# 02-CPU.net
KiCad netlist of a schematic drawn in Altium Designer
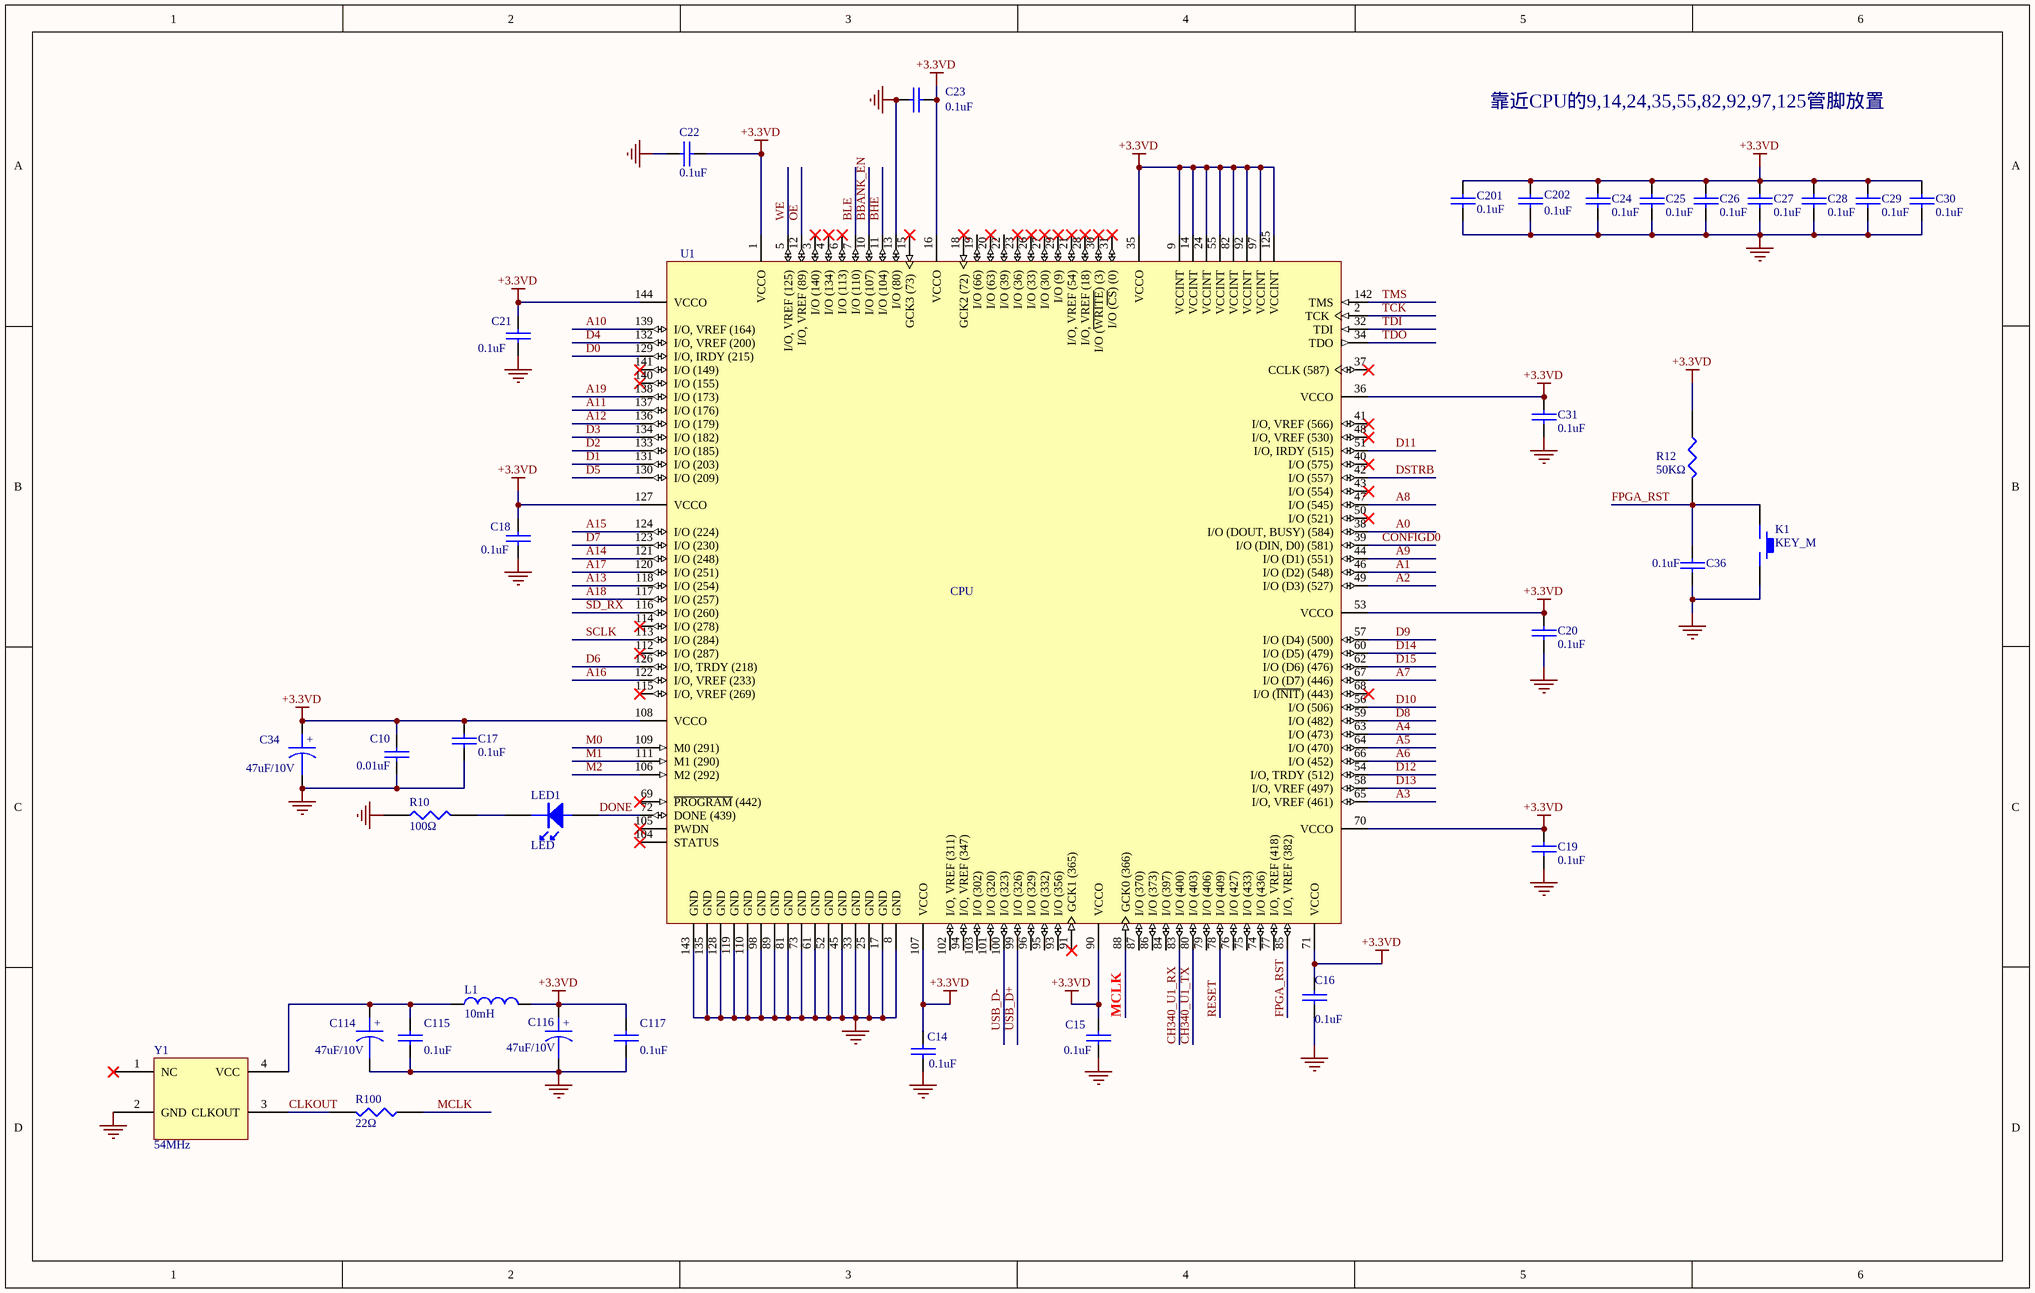
[diagram p0: 02-CPU.schdoc]

(export (version "E")
  (design (tool "Eeschema 10.0.6"))
  (components
    (comp (ref "C10")
      (value "0.01uF")
      (footprint "0603")
      (description "Capacitor")
      (libsource (lib "*") (part "CAP"))
    )
    (comp (ref "C14")
      (value "0.1uF")
      (footprint "0603")
      (description "Capacitor")
      (libsource (lib "*") (part "CAP"))
    )
    (comp (ref "C15")
      (value "0.1uF")
      (footprint "0603")
      (description "Capacitor")
      (libsource (lib "*") (part "CAP"))
    )
    (comp (ref "C16")
      (value "0.1uF")
      (footprint "0603")
      (description "Capacitor")
      (libsource (lib "*") (part "CAP"))
    )
    (comp (ref "C17")
      (value "0.1uF")
      (footprint "0603")
      (description "Capacitor")
      (libsource (lib "*") (part "CAP"))
    )
    (comp (ref "C18")
      (value "0.1uF")
      (footprint "0603")
      (description "Capacitor")
      (libsource (lib "*") (part "CAP"))
    )
    (comp (ref "C19")
      (value "0.1uF")
      (footprint "0603")
      (description "Capacitor")
      (libsource (lib "*") (part "CAP"))
    )
    (comp (ref "C20")
      (value "0.1uF")
      (footprint "0603")
      (description "Capacitor")
      (libsource (lib "*") (part "CAP"))
    )
    (comp (ref "C21")
      (value "0.1uF")
      (footprint "0603")
      (description "Capacitor")
      (libsource (lib "*") (part "CAP"))
    )
    (comp (ref "C22")
      (value "0.1uF")
      (footprint "0603")
      (description "Capacitor")
      (libsource (lib "*") (part "CAP"))
    )
    (comp (ref "C23")
      (value "0.1uF")
      (footprint "0603")
      (description "Capacitor")
      (libsource (lib "*") (part "CAP"))
    )
    (comp (ref "C24")
      (value "0.1uF")
      (footprint "0603")
      (description "Capacitor")
      (libsource (lib "*") (part "CAP"))
    )
    (comp (ref "C25")
      (value "0.1uF")
      (footprint "0603")
      (description "Capacitor")
      (libsource (lib "*") (part "CAP"))
    )
    (comp (ref "C26")
      (value "0.1uF")
      (footprint "0603")
      (description "Capacitor")
      (libsource (lib "*") (part "CAP"))
    )
    (comp (ref "C27")
      (value "0.1uF")
      (footprint "0603")
      (description "Capacitor")
      (libsource (lib "*") (part "CAP"))
    )
    (comp (ref "C28")
      (value "0.1uF")
      (footprint "0603")
      (description "Capacitor")
      (libsource (lib "*") (part "CAP"))
    )
    (comp (ref "C29")
      (value "0.1uF")
      (footprint "0603")
      (description "Capacitor")
      (libsource (lib "*") (part "CAP"))
    )
    (comp (ref "C30")
      (value "0.1uF")
      (footprint "0603")
      (description "Capacitor")
      (libsource (lib "*") (part "CAP"))
    )
    (comp (ref "C31")
      (value "0.1uF")
      (footprint "0603")
      (description "Capacitor")
      (libsource (lib "*") (part "CAP"))
    )
    (comp (ref "C34")
      (value "47uF/10V")
      (footprint "CAK45-E")
      (description "Capacitor")
      (libsource (lib "*") (part "CAPACITOR POL"))
    )
    (comp (ref "C36")
      (value "0.1uF")
      (footprint "0603")
      (description "Capacitor")
      (libsource (lib "*") (part "CAP"))
    )
    (comp (ref "C114")
      (value "47uF/10V")
      (footprint "CAK45-E")
      (description "Capacitor")
      (libsource (lib "*") (part "CAPACITOR POL"))
    )
    (comp (ref "C115")
      (value "0.1uF")
      (footprint "0603")
      (description "Capacitor")
      (libsource (lib "*") (part "CAP"))
    )
    (comp (ref "C116")
      (value "47uF/10V")
      (footprint "CAK45-E")
      (description "Capacitor")
      (libsource (lib "*") (part "CAPACITOR POL"))
    )
    (comp (ref "C117")
      (value "0.1uF")
      (footprint "0603")
      (description "Capacitor")
      (libsource (lib "*") (part "CAP"))
    )
    (comp (ref "C201")
      (value "0.1uF")
      (footprint "0603")
      (description "Capacitor")
      (libsource (lib "*") (part "CAP"))
    )
    (comp (ref "C202")
      (value "0.1uF")
      (footprint "0603")
      (description "Capacitor")
      (libsource (lib "*") (part "CAP"))
    )
    (comp (ref "K1")
      (value "KEY_M")
      (footprint "SWITCH")
      (libsource (lib "Miscellaneous Devices") (part "KEY_M"))
    )
    (comp (ref "L1")
      (value "10mH")
      (footprint "L0805")
      (description "Inductor")
      (fields (field (name "PUBLISHER") "Altium Limited"))
      (libsource (lib "Miscellaneous Devices") (part "Inductor"))
    )
    (comp (ref "LED1") (value "LED") (footprint "LED0805") (libsource (lib "*") (part "LED")))
    (comp (ref "R10") (value "100Ω") (footprint "0805") (libsource (lib "*") (part "RES1")))
    (comp (ref "R12") (value "50KΩ") (footprint "0805") (libsource (lib "*") (part "RES1")))
    (comp (ref "R100") (value "22Ω") (footprint "0805") (libsource (lib "*") (part "RES1")))
    (comp (ref "U1")
      (value "CPU")
      (footprint "F-QFP20X20-G144/N")
      (description "Spartan-II 2.5V Field Programmable Gate Array")
      (libsource (lib "*") (part "XC2S50-6TQ144C"))
    )
    (comp (ref "Y1")
      (value "54MHz")
      (footprint "7050晶振")
      (description "active oscillation")
      (libsource (lib "*") (part "OSC"))
    )
  )
  (nets
    (net (code "1") (name "+3.3VD") (class "Default")
      (node (ref "C10") (pin "1") (pinfunction "1_1") (pintype "passive"))
      (node (ref "C116") (pin "1") (pinfunction "1_1") (pintype "passive"))
      (node (ref "C117") (pin "1") (pinfunction "1_1") (pintype "passive"))
      (node (ref "C14") (pin "1") (pinfunction "1_1") (pintype "passive"))
      (node (ref "C15") (pin "2") (pinfunction "2_2") (pintype "passive"))
      (node (ref "C16") (pin "2") (pinfunction "2_2") (pintype "passive"))
      (node (ref "C17") (pin "1") (pinfunction "1_1") (pintype "passive"))
      (node (ref "C18") (pin "1") (pinfunction "1_1") (pintype "passive"))
      (node (ref "C19") (pin "2") (pinfunction "2_2") (pintype "passive"))
      (node (ref "C20") (pin "2") (pinfunction "2_2") (pintype "passive"))
      (node (ref "C201") (pin "1") (pinfunction "1_1") (pintype "passive"))
      (node (ref "C202") (pin "1") (pinfunction "1_1") (pintype "passive"))
      (node (ref "C21") (pin "2") (pinfunction "2_2") (pintype "passive"))
      (node (ref "C22") (pin "1") (pinfunction "1_1") (pintype "passive"))
      (node (ref "C23") (pin "1") (pinfunction "1_1") (pintype "passive"))
      (node (ref "C24") (pin "1") (pinfunction "1_1") (pintype "passive"))
      (node (ref "C25") (pin "1") (pinfunction "1_1") (pintype "passive"))
      (node (ref "C26") (pin "1") (pinfunction "1_1") (pintype "passive"))
      (node (ref "C27") (pin "1") (pinfunction "1_1") (pintype "passive"))
      (node (ref "C28") (pin "1") (pinfunction "1_1") (pintype "passive"))
      (node (ref "C29") (pin "1") (pinfunction "1_1") (pintype "passive"))
      (node (ref "C30") (pin "1") (pinfunction "1_1") (pintype "passive"))
      (node (ref "C31") (pin "2") (pinfunction "2_2") (pintype "passive"))
      (node (ref "C34") (pin "1") (pinfunction "1_1") (pintype "passive"))
      (node (ref "L1") (pin "2") (pinfunction "2_2") (pintype "passive"))
      (node (ref "R12") (pin "1") (pinfunction "1_1") (pintype "passive"))
      (node (ref "U1") (pin "1") (pinfunction "VCCO_1") (pintype "power_in"))
      (node (ref "U1") (pin "107") (pinfunction "VCCO_107") (pintype "power_in"))
      (node (ref "U1") (pin "108") (pinfunction "VCCO_108") (pintype "power_in"))
      (node (ref "U1") (pin "125") (pinfunction "VCCINT_125") (pintype "power_in"))
      (node (ref "U1") (pin "127") (pinfunction "VCCO_127") (pintype "power_in"))
      (node (ref "U1") (pin "14") (pinfunction "VCCINT_14") (pintype "power_in"))
      (node (ref "U1") (pin "144") (pinfunction "VCCO_144") (pintype "power_in"))
      (node (ref "U1") (pin "16") (pinfunction "VCCO_16") (pintype "power_in"))
      (node (ref "U1") (pin "24") (pinfunction "VCCINT_24") (pintype "power_in"))
      (node (ref "U1") (pin "35") (pinfunction "VCCO_35") (pintype "power_in"))
      (node (ref "U1") (pin "36") (pinfunction "VCCO_36") (pintype "power_in"))
      (node (ref "U1") (pin "53") (pinfunction "VCCO_53") (pintype "power_in"))
      (node (ref "U1") (pin "55") (pinfunction "VCCINT_55") (pintype "power_in"))
      (node (ref "U1") (pin "70") (pinfunction "VCCO_70") (pintype "power_in"))
      (node (ref "U1") (pin "71") (pinfunction "VCCO_71") (pintype "power_in"))
      (node (ref "U1") (pin "82") (pinfunction "VCCINT_82") (pintype "power_in"))
      (node (ref "U1") (pin "9") (pinfunction "VCCINT_9") (pintype "power_in"))
      (node (ref "U1") (pin "90") (pinfunction "VCCO_90") (pintype "power_in"))
      (node (ref "U1") (pin "92") (pinfunction "VCCINT_92") (pintype "power_in"))
      (node (ref "U1") (pin "97") (pinfunction "VCCINT_97") (pintype "power_in"))
    )
    (net (code "2") (name "/A0") (class "Default")
      (node (ref "U1") (pin "38") (pinfunction "I/O_(DOUT,_BUSY)_(584)_38") (pintype "bidirectional"))
    )
    (net (code "3") (name "/A1") (class "Default")
      (node (ref "U1") (pin "46") (pinfunction "I/O_(D2)_(548)_46") (pintype "bidirectional"))
    )
    (net (code "4") (name "/A2") (class "Default")
      (node (ref "U1") (pin "49") (pinfunction "I/O_(D3)_(527)_49") (pintype "bidirectional"))
    )
    (net (code "5") (name "/A3") (class "Default")
      (node (ref "U1") (pin "65") (pinfunction "I/O,_VREF_(461)_65") (pintype "bidirectional"))
    )
    (net (code "6") (name "/A4") (class "Default")
      (node (ref "U1") (pin "63") (pinfunction "I/O_(473)_63") (pintype "bidirectional"))
    )
    (net (code "7") (name "/A5") (class "Default")
      (node (ref "U1") (pin "64") (pinfunction "I/O_(470)_64") (pintype "bidirectional"))
    )
    (net (code "8") (name "/A6") (class "Default")
      (node (ref "U1") (pin "66") (pinfunction "I/O_(452)_66") (pintype "bidirectional"))
    )
    (net (code "9") (name "/A7") (class "Default")
      (node (ref "U1") (pin "67") (pinfunction "I/O_(D7)_(446)_67") (pintype "bidirectional"))
    )
    (net (code "10") (name "/A8") (class "Default")
      (node (ref "U1") (pin "47") (pinfunction "I/O_(545)_47") (pintype "bidirectional"))
    )
    (net (code "11") (name "/A9") (class "Default")
      (node (ref "U1") (pin "44") (pinfunction "I/O_(D1)_(551)_44") (pintype "bidirectional"))
    )
    (net (code "12") (name "/A10") (class "Default")
      (node (ref "U1") (pin "139") (pinfunction "I/O,_VREF_(164)_139") (pintype "bidirectional"))
    )
    (net (code "13") (name "/A11") (class "Default")
      (node (ref "U1") (pin "137") (pinfunction "I/O_(176)_137") (pintype "bidirectional"))
    )
    (net (code "14") (name "/A12") (class "Default")
      (node (ref "U1") (pin "136") (pinfunction "I/O_(179)_136") (pintype "bidirectional"))
    )
    (net (code "15") (name "/A13") (class "Default")
      (node (ref "U1") (pin "118") (pinfunction "I/O_(254)_118") (pintype "bidirectional"))
    )
    (net (code "16") (name "/A14") (class "Default")
      (node (ref "U1") (pin "121") (pinfunction "I/O_(248)_121") (pintype "bidirectional"))
    )
    (net (code "17") (name "/A15") (class "Default")
      (node (ref "U1") (pin "124") (pinfunction "I/O_(224)_124") (pintype "bidirectional"))
    )
    (net (code "18") (name "/A16") (class "Default")
      (node (ref "U1") (pin "122") (pinfunction "I/O,_VREF_(233)_122") (pintype "bidirectional"))
    )
    (net (code "19") (name "/A17") (class "Default")
      (node (ref "U1") (pin "120") (pinfunction "I/O_(251)_120") (pintype "bidirectional"))
    )
    (net (code "20") (name "/A18") (class "Default")
      (node (ref "U1") (pin "117") (pinfunction "I/O_(257)_117") (pintype "bidirectional"))
    )
    (net (code "21") (name "/A19") (class "Default")
      (node (ref "U1") (pin "138") (pinfunction "I/O_(173)_138") (pintype "bidirectional"))
    )
    (net (code "22") (name "/BBANK_EN") (class "Default")
      (node (ref "U1") (pin "10") (pinfunction "I/O_(107)_10") (pintype "bidirectional"))
    )
    (net (code "23") (name "/BHE") (class "Default")
      (node (ref "U1") (pin "11") (pinfunction "I/O_(104)_11") (pintype "bidirectional"))
    )
    (net (code "24") (name "/BLE") (class "Default")
      (node (ref "U1") (pin "7") (pinfunction "I/O_(110)_7") (pintype "bidirectional"))
    )
    (net (code "25") (name "/CH340_U1_RX") (class "Default")
      (node (ref "U1") (pin "83") (pinfunction "I/O_(400)_83") (pintype "bidirectional"))
    )
    (net (code "26") (name "/CH340_U1_TX") (class "Default")
      (node (ref "U1") (pin "80") (pinfunction "I/O_(403)_80") (pintype "bidirectional"))
    )
    (net (code "27") (name "/CLKOUT") (class "Default")
      (node (ref "R100") (pin "2") (pinfunction "2_2") (pintype "passive"))
      (node (ref "Y1") (pin "3") (pinfunction "CLKOUT_3") (pintype "passive"))
    )
    (net (code "28") (name "/CONFIGD0") (class "Default")
      (node (ref "U1") (pin "39") (pinfunction "I/O_(DIN,_D0)_(581)_39") (pintype "bidirectional"))
    )
    (net (code "29") (name "/D0") (class "Default")
      (node (ref "U1") (pin "129") (pinfunction "I/O,_IRDY_(215)_129") (pintype "bidirectional"))
    )
    (net (code "30") (name "/D1") (class "Default")
      (node (ref "U1") (pin "131") (pinfunction "I/O_(203)_131") (pintype "bidirectional"))
    )
    (net (code "31") (name "/D2") (class "Default")
      (node (ref "U1") (pin "133") (pinfunction "I/O_(185)_133") (pintype "bidirectional"))
    )
    (net (code "32") (name "/D3") (class "Default")
      (node (ref "U1") (pin "134") (pinfunction "I/O_(182)_134") (pintype "bidirectional"))
    )
    (net (code "33") (name "/D4") (class "Default")
      (node (ref "U1") (pin "132") (pinfunction "I/O,_VREF_(200)_132") (pintype "bidirectional"))
    )
    (net (code "34") (name "/D5") (class "Default")
      (node (ref "U1") (pin "130") (pinfunction "I/O_(209)_130") (pintype "bidirectional"))
    )
    (net (code "35") (name "/D6") (class "Default")
      (node (ref "U1") (pin "126") (pinfunction "I/O,_TRDY_(218)_126") (pintype "bidirectional"))
    )
    (net (code "36") (name "/D7") (class "Default")
      (node (ref "U1") (pin "123") (pinfunction "I/O_(230)_123") (pintype "bidirectional"))
    )
    (net (code "37") (name "/D8") (class "Default")
      (node (ref "U1") (pin "59") (pinfunction "I/O_(482)_59") (pintype "bidirectional"))
    )
    (net (code "38") (name "/D9") (class "Default")
      (node (ref "U1") (pin "57") (pinfunction "I/O_(D4)_(500)_57") (pintype "bidirectional"))
    )
    (net (code "39") (name "/D10") (class "Default")
      (node (ref "U1") (pin "56") (pinfunction "I/O_(506)_56") (pintype "bidirectional"))
    )
    (net (code "40") (name "/D11") (class "Default")
      (node (ref "U1") (pin "51") (pinfunction "I/O,_IRDY_(515)_51") (pintype "bidirectional"))
    )
    (net (code "41") (name "/D12") (class "Default")
      (node (ref "U1") (pin "54") (pinfunction "I/O,_TRDY_(512)_54") (pintype "bidirectional"))
    )
    (net (code "42") (name "/D13") (class "Default")
      (node (ref "U1") (pin "58") (pinfunction "I/O,_VREF_(497)_58") (pintype "bidirectional"))
    )
    (net (code "43") (name "/D14") (class "Default")
      (node (ref "U1") (pin "60") (pinfunction "I/O_(D5)_(479)_60") (pintype "bidirectional"))
    )
    (net (code "44") (name "/D15") (class "Default")
      (node (ref "U1") (pin "62") (pinfunction "I/O_(D6)_(476)_62") (pintype "bidirectional"))
    )
    (net (code "45") (name "/DONE") (class "Default")
      (node (ref "LED1") (pin "1") (pinfunction "A_1") (pintype "passive"))
      (node (ref "U1") (pin "72") (pinfunction "DONE_(439)_72") (pintype "bidirectional"))
    )
    (net (code "46") (name "/DSTRB") (class "Default")
      (node (ref "U1") (pin "42") (pinfunction "I/O_(557)_42") (pintype "bidirectional"))
    )
    (net (code "47") (name "/FPGA_RST") (class "Default")
      (node (ref "C36") (pin "2") (pinfunction "2_2") (pintype "passive"))
      (node (ref "K1") (pin "1") (pinfunction "1_1") (pintype "passive"))
      (node (ref "R12") (pin "2") (pinfunction "2_2") (pintype "passive"))
      (node (ref "U1") (pin "85") (pinfunction "I/O,_VREF_(382)_85") (pintype "bidirectional"))
    )
    (net (code "48") (name "/M0") (class "Default")
      (node (ref "U1") (pin "109") (pinfunction "M0_(291)_109") (pintype "input"))
    )
    (net (code "49") (name "/M1") (class "Default")
      (node (ref "U1") (pin "111") (pinfunction "M1_(290)_111") (pintype "input"))
    )
    (net (code "50") (name "/M2") (class "Default")
      (node (ref "U1") (pin "106") (pinfunction "M2_(292)_106") (pintype "input"))
    )
    (net (code "51") (name "/MCLK") (class "Default")
      (node (ref "R100") (pin "1") (pinfunction "1_1") (pintype "passive"))
      (node (ref "U1") (pin "88") (pinfunction "GCK0_(366)_88") (pintype "input"))
    )
    (net (code "52") (name "/OE") (class "Default")
      (node (ref "U1") (pin "12") (pinfunction "I/O,_VREF_(89)_12") (pintype "bidirectional"))
    )
    (net (code "53") (name "/RESET") (class "Default")
      (node (ref "U1") (pin "78") (pinfunction "I/O_(409)_78") (pintype "bidirectional"))
    )
    (net (code "54") (name "/SCLK") (class "Default")
      (node (ref "U1") (pin "113") (pinfunction "I/O_(284)_113") (pintype "bidirectional"))
    )
    (net (code "55") (name "/SD_RX") (class "Default")
      (node (ref "U1") (pin "116") (pinfunction "I/O_(260)_116") (pintype "bidirectional"))
    )
    (net (code "56") (name "/TCK") (class "Default")
      (node (ref "U1") (pin "2") (pinfunction "TCK_2") (pintype "input"))
    )
    (net (code "57") (name "/TDI") (class "Default")
      (node (ref "U1") (pin "32") (pinfunction "TDI_32") (pintype "input"))
    )
    (net (code "58") (name "/TDO") (class "Default")
      (node (ref "U1") (pin "34") (pinfunction "TDO_34") (pintype "output"))
    )
    (net (code "59") (name "/TMS") (class "Default")
      (node (ref "U1") (pin "142") (pinfunction "TMS_142") (pintype "input"))
    )
    (net (code "60") (name "/USB_D+") (class "Default")
      (node (ref "U1") (pin "99") (pinfunction "I/O_(326)_99") (pintype "bidirectional"))
    )
    (net (code "61") (name "/USB_D-") (class "Default")
      (node (ref "U1") (pin "100") (pinfunction "I/O_(323)_100") (pintype "bidirectional"))
    )
    (net (code "62") (name "/WE") (class "Default")
      (node (ref "U1") (pin "5") (pinfunction "I/O,_VREF_(125)_5") (pintype "bidirectional"))
    )
    (net (code "63") (name "DGND") (class "Default")
      (node (ref "C10") (pin "2") (pinfunction "2_2") (pintype "passive"))
      (node (ref "C114") (pin "2") (pinfunction "2_2") (pintype "passive"))
      (node (ref "C115") (pin "2") (pinfunction "2_2") (pintype "passive"))
      (node (ref "C116") (pin "2") (pinfunction "2_2") (pintype "passive"))
      (node (ref "C117") (pin "2") (pinfunction "2_2") (pintype "passive"))
      (node (ref "C14") (pin "2") (pinfunction "2_2") (pintype "passive"))
      (node (ref "C15") (pin "1") (pinfunction "1_1") (pintype "passive"))
      (node (ref "C16") (pin "1") (pinfunction "1_1") (pintype "passive"))
      (node (ref "C17") (pin "2") (pinfunction "2_2") (pintype "passive"))
      (node (ref "C18") (pin "2") (pinfunction "2_2") (pintype "passive"))
      (node (ref "C19") (pin "1") (pinfunction "1_1") (pintype "passive"))
      (node (ref "C20") (pin "1") (pinfunction "1_1") (pintype "passive"))
      (node (ref "C201") (pin "2") (pinfunction "2_2") (pintype "passive"))
      (node (ref "C202") (pin "2") (pinfunction "2_2") (pintype "passive"))
      (node (ref "C21") (pin "1") (pinfunction "1_1") (pintype "passive"))
      (node (ref "C22") (pin "2") (pinfunction "2_2") (pintype "passive"))
      (node (ref "C23") (pin "2") (pinfunction "2_2") (pintype "passive"))
      (node (ref "C24") (pin "2") (pinfunction "2_2") (pintype "passive"))
      (node (ref "C25") (pin "2") (pinfunction "2_2") (pintype "passive"))
      (node (ref "C26") (pin "2") (pinfunction "2_2") (pintype "passive"))
      (node (ref "C27") (pin "2") (pinfunction "2_2") (pintype "passive"))
      (node (ref "C28") (pin "2") (pinfunction "2_2") (pintype "passive"))
      (node (ref "C29") (pin "2") (pinfunction "2_2") (pintype "passive"))
      (node (ref "C30") (pin "2") (pinfunction "2_2") (pintype "passive"))
      (node (ref "C31") (pin "1") (pinfunction "1_1") (pintype "passive"))
      (node (ref "C34") (pin "2") (pinfunction "2_2") (pintype "passive"))
      (node (ref "C36") (pin "1") (pinfunction "1_1") (pintype "passive"))
      (node (ref "K1") (pin "2") (pinfunction "2_2") (pintype "passive"))
      (node (ref "R10") (pin "1") (pinfunction "1_1") (pintype "passive"))
      (node (ref "U1") (pin "110") (pinfunction "GND_110") (pintype "power_in"))
      (node (ref "U1") (pin "119") (pinfunction "GND_119") (pintype "power_in"))
      (node (ref "U1") (pin "128") (pinfunction "GND_128") (pintype "power_in"))
      (node (ref "U1") (pin "13") (pinfunction "I/O_(80)_13") (pintype "bidirectional"))
      (node (ref "U1") (pin "135") (pinfunction "GND_135") (pintype "power_in"))
      (node (ref "U1") (pin "143") (pinfunction "GND_143") (pintype "power_in"))
      (node (ref "U1") (pin "17") (pinfunction "GND_17") (pintype "power_in"))
      (node (ref "U1") (pin "25") (pinfunction "GND_25") (pintype "power_in"))
      (node (ref "U1") (pin "33") (pinfunction "GND_33") (pintype "power_in"))
      (node (ref "U1") (pin "45") (pinfunction "GND_45") (pintype "power_in"))
      (node (ref "U1") (pin "52") (pinfunction "GND_52") (pintype "power_in"))
      (node (ref "U1") (pin "61") (pinfunction "GND_61") (pintype "power_in"))
      (node (ref "U1") (pin "73") (pinfunction "GND_73") (pintype "power_in"))
      (node (ref "U1") (pin "8") (pinfunction "GND_8") (pintype "power_in"))
      (node (ref "U1") (pin "81") (pinfunction "GND_81") (pintype "power_in"))
      (node (ref "U1") (pin "89") (pinfunction "GND_89") (pintype "power_in"))
      (node (ref "U1") (pin "98") (pinfunction "GND_98") (pintype "power_in"))
      (node (ref "Y1") (pin "2") (pinfunction "GND_2") (pintype "passive"))
    )
    (net (code "64") (name "Net-(LED1-K)") (class "Default")
      (node (ref "LED1") (pin "2") (pinfunction "K_2") (pintype "passive"))
      (node (ref "R10") (pin "2") (pinfunction "2_2") (pintype "passive"))
    )
    (net (code "65") (name "Net-(Y1-VCC)") (class "Default")
      (node (ref "C114") (pin "1") (pinfunction "1_1") (pintype "passive"))
      (node (ref "C115") (pin "1") (pinfunction "1_1") (pintype "passive"))
      (node (ref "L1") (pin "1") (pinfunction "1_1") (pintype "passive"))
      (node (ref "Y1") (pin "4") (pinfunction "VCC_4") (pintype "passive"))
    )
    (net (code "66") (name "unconnected-(U1-CCLK_(587)-Pad37)") (class "Default")
      (node (ref "U1") (pin "37") (pinfunction "CCLK_(587)_37") (pintype "bidirectional+no_connect"))
    )
    (net (code "67") (name "unconnected-(U1-GCK1_(365)-Pad91)") (class "Default")
      (node (ref "U1") (pin "91") (pinfunction "GCK1_(365)_91") (pintype "input+no_connect"))
    )
    (net (code "68") (name "unconnected-(U1-GCK2_(72)-Pad18)") (class "Default")
      (node (ref "U1") (pin "18") (pinfunction "GCK2_(72)_18") (pintype "input+no_connect"))
    )
    (net (code "69") (name "unconnected-(U1-GCK3_(73)-Pad15)") (class "Default")
      (node (ref "U1") (pin "15") (pinfunction "GCK3_(73)_15") (pintype "input+no_connect"))
    )
    (net (code "70") (name "unconnected-(U1-I{slash}O,_VREF_(18)-Pad28)") (class "Default")
      (node (ref "U1") (pin "28") (pinfunction "I/O,_VREF_(18)_28") (pintype "bidirectional+no_connect"))
    )
    (net (code "71") (name "unconnected-(U1-I{slash}O,_VREF_(54)-Pad21)") (class "Default")
      (node (ref "U1") (pin "21") (pinfunction "I/O,_VREF_(54)_21") (pintype "bidirectional+no_connect"))
    )
    (net (code "72") (name "unconnected-(U1-I{slash}O,_VREF_(269)-Pad115)") (class "Default")
      (node (ref "U1") (pin "115") (pinfunction "I/O,_VREF_(269)_115") (pintype "bidirectional+no_connect"))
    )
    (net (code "73") (name "unconnected-(U1-I{slash}O,_VREF_(311)-Pad102)") (class "Default")
      (node (ref "U1") (pin "102") (pinfunction "I/O,_VREF_(311)_102") (pintype "bidirectional"))
    )
    (net (code "74") (name "unconnected-(U1-I{slash}O,_VREF_(347)-Pad94)") (class "Default")
      (node (ref "U1") (pin "94") (pinfunction "I/O,_VREF_(347)_94") (pintype "bidirectional"))
    )
    (net (code "75") (name "unconnected-(U1-I{slash}O,_VREF_(418)-Pad77)") (class "Default")
      (node (ref "U1") (pin "77") (pinfunction "I/O,_VREF_(418)_77") (pintype "bidirectional"))
    )
    (net (code "76") (name "unconnected-(U1-I{slash}O,_VREF_(530)-Pad48)") (class "Default")
      (node (ref "U1") (pin "48") (pinfunction "I/O,_VREF_(530)_48") (pintype "bidirectional+no_connect"))
    )
    (net (code "77") (name "unconnected-(U1-I{slash}O,_VREF_(566)-Pad41)") (class "Default")
      (node (ref "U1") (pin "41") (pinfunction "I/O,_VREF_(566)_41") (pintype "bidirectional+no_connect"))
    )
    (net (code "78") (name "unconnected-(U1-I{slash}O_(9)-Pad29)") (class "Default")
      (node (ref "U1") (pin "29") (pinfunction "I/O_(9)_29") (pintype "bidirectional+no_connect"))
    )
    (net (code "79") (name "unconnected-(U1-I{slash}O_(30)-Pad27)") (class "Default")
      (node (ref "U1") (pin "27") (pinfunction "I/O_(30)_27") (pintype "bidirectional+no_connect"))
    )
    (net (code "80") (name "unconnected-(U1-I{slash}O_(33)-Pad26)") (class "Default")
      (node (ref "U1") (pin "26") (pinfunction "I/O_(33)_26") (pintype "bidirectional+no_connect"))
    )
    (net (code "81") (name "unconnected-(U1-I{slash}O_(36)-Pad23)") (class "Default")
      (node (ref "U1") (pin "23") (pinfunction "I/O_(36)_23") (pintype "bidirectional+no_connect"))
    )
    (net (code "82") (name "unconnected-(U1-I{slash}O_(39)-Pad22)") (class "Default")
      (node (ref "U1") (pin "22") (pinfunction "I/O_(39)_22") (pintype "bidirectional"))
    )
    (net (code "83") (name "unconnected-(U1-I{slash}O_(63)-Pad20)") (class "Default")
      (node (ref "U1") (pin "20") (pinfunction "I/O_(63)_20") (pintype "bidirectional+no_connect"))
    )
    (net (code "84") (name "unconnected-(U1-I{slash}O_(66)-Pad19)") (class "Default")
      (node (ref "U1") (pin "19") (pinfunction "I/O_(66)_19") (pintype "bidirectional"))
    )
    (net (code "85") (name "unconnected-(U1-I{slash}O_(113)-Pad6)") (class "Default")
      (node (ref "U1") (pin "6") (pinfunction "I/O_(113)_6") (pintype "bidirectional+no_connect"))
    )
    (net (code "86") (name "unconnected-(U1-I{slash}O_(134)-Pad4)") (class "Default")
      (node (ref "U1") (pin "4") (pinfunction "I/O_(134)_4") (pintype "bidirectional+no_connect"))
    )
    (net (code "87") (name "unconnected-(U1-I{slash}O_(140)-Pad3)") (class "Default")
      (node (ref "U1") (pin "3") (pinfunction "I/O_(140)_3") (pintype "bidirectional+no_connect"))
    )
    (net (code "88") (name "unconnected-(U1-I{slash}O_(149)-Pad141)") (class "Default")
      (node (ref "U1") (pin "141") (pinfunction "I/O_(149)_141") (pintype "bidirectional+no_connect"))
    )
    (net (code "89") (name "unconnected-(U1-I{slash}O_(155)-Pad140)") (class "Default")
      (node (ref "U1") (pin "140") (pinfunction "I/O_(155)_140") (pintype "bidirectional+no_connect"))
    )
    (net (code "90") (name "unconnected-(U1-I{slash}O_(278)-Pad114)") (class "Default")
      (node (ref "U1") (pin "114") (pinfunction "I/O_(278)_114") (pintype "bidirectional+no_connect"))
    )
    (net (code "91") (name "unconnected-(U1-I{slash}O_(287)-Pad112)") (class "Default")
      (node (ref "U1") (pin "112") (pinfunction "I/O_(287)_112") (pintype "bidirectional+no_connect"))
    )
    (net (code "92") (name "unconnected-(U1-I{slash}O_(302)-Pad103)") (class "Default")
      (node (ref "U1") (pin "103") (pinfunction "I/O_(302)_103") (pintype "bidirectional"))
    )
    (net (code "93") (name "unconnected-(U1-I{slash}O_(320)-Pad101)") (class "Default")
      (node (ref "U1") (pin "101") (pinfunction "I/O_(320)_101") (pintype "bidirectional"))
    )
    (net (code "94") (name "unconnected-(U1-I{slash}O_(329)-Pad96)") (class "Default")
      (node (ref "U1") (pin "96") (pinfunction "I/O_(329)_96") (pintype "bidirectional"))
    )
    (net (code "95") (name "unconnected-(U1-I{slash}O_(332)-Pad95)") (class "Default")
      (node (ref "U1") (pin "95") (pinfunction "I/O_(332)_95") (pintype "bidirectional"))
    )
    (net (code "96") (name "unconnected-(U1-I{slash}O_(356)-Pad93)") (class "Default")
      (node (ref "U1") (pin "93") (pinfunction "I/O_(356)_93") (pintype "bidirectional"))
    )
    (net (code "97") (name "unconnected-(U1-I{slash}O_(370)-Pad87)") (class "Default")
      (node (ref "U1") (pin "87") (pinfunction "I/O_(370)_87") (pintype "bidirectional"))
    )
    (net (code "98") (name "unconnected-(U1-I{slash}O_(373)-Pad86)") (class "Default")
      (node (ref "U1") (pin "86") (pinfunction "I/O_(373)_86") (pintype "bidirectional"))
    )
    (net (code "99") (name "unconnected-(U1-I{slash}O_(397)-Pad84)") (class "Default")
      (node (ref "U1") (pin "84") (pinfunction "I/O_(397)_84") (pintype "bidirectional"))
    )
    (net (code "100") (name "unconnected-(U1-I{slash}O_(406)-Pad79)") (class "Default")
      (node (ref "U1") (pin "79") (pinfunction "I/O_(406)_79") (pintype "bidirectional"))
    )
    (net (code "101") (name "unconnected-(U1-I{slash}O_(427)-Pad76)") (class "Default")
      (node (ref "U1") (pin "76") (pinfunction "I/O_(427)_76") (pintype "bidirectional"))
    )
    (net (code "102") (name "unconnected-(U1-I{slash}O_(433)-Pad75)") (class "Default")
      (node (ref "U1") (pin "75") (pinfunction "I/O_(433)_75") (pintype "bidirectional"))
    )
    (net (code "103") (name "unconnected-(U1-I{slash}O_(436)-Pad74)") (class "Default")
      (node (ref "U1") (pin "74") (pinfunction "I/O_(436)_74") (pintype "bidirectional"))
    )
    (net (code "104") (name "unconnected-(U1-I{slash}O_(521)-Pad50)") (class "Default")
      (node (ref "U1") (pin "50") (pinfunction "I/O_(521)_50") (pintype "bidirectional+no_connect"))
    )
    (net (code "105") (name "unconnected-(U1-I{slash}O_(554)-Pad43)") (class "Default")
      (node (ref "U1") (pin "43") (pinfunction "I/O_(554)_43") (pintype "bidirectional+no_connect"))
    )
    (net (code "106") (name "unconnected-(U1-I{slash}O_(575)-Pad40)") (class "Default")
      (node (ref "U1") (pin "40") (pinfunction "I/O_(575)_40") (pintype "bidirectional+no_connect"))
    )
    (net (code "107") (name "unconnected-(U1-I{slash}O_(~{CS})_(0)-Pad31)") (class "Default")
      (node (ref "U1") (pin "31") (pinfunction "I/O_(~{CS})_(0)_31") (pintype "bidirectional+no_connect"))
    )
    (net (code "108") (name "unconnected-(U1-I{slash}O_(~{INIT})_(443)-Pad68)") (class "Default")
      (node (ref "U1") (pin "68") (pinfunction "I/O_(~{INIT})_(443)_68") (pintype "bidirectional+no_connect"))
    )
    (net (code "109") (name "unconnected-(U1-I{slash}O_(~{WRITE})_(3)-Pad30)") (class "Default")
      (node (ref "U1") (pin "30") (pinfunction "I/O_(~{WRITE})_(3)_30") (pintype "bidirectional+no_connect"))
    )
    (net (code "110") (name "unconnected-(U1-PWDN-Pad105)") (class "Default")
      (node (ref "U1") (pin "105") (pinfunction "PWDN_105") (pintype "passive+no_connect"))
    )
    (net (code "111") (name "unconnected-(U1-STATUS-Pad104)") (class "Default")
      (node (ref "U1") (pin "104") (pinfunction "STATUS_104") (pintype "passive+no_connect"))
    )
    (net (code "112") (name "unconnected-(U1-~{PROGRAM}_(442)-Pad69)") (class "Default")
      (node (ref "U1") (pin "69") (pinfunction "~{PROGRAM}_(442)_69") (pintype "input+no_connect"))
    )
    (net (code "113") (name "unconnected-(Y1-NC-Pad1)") (class "Default")
      (node (ref "Y1") (pin "1") (pinfunction "NC_1") (pintype "passive+no_connect"))
    )
  )
)
